# 0_96OLED_SSD1315.net
KiCad netlist of a schematic drawn in Altium Designer
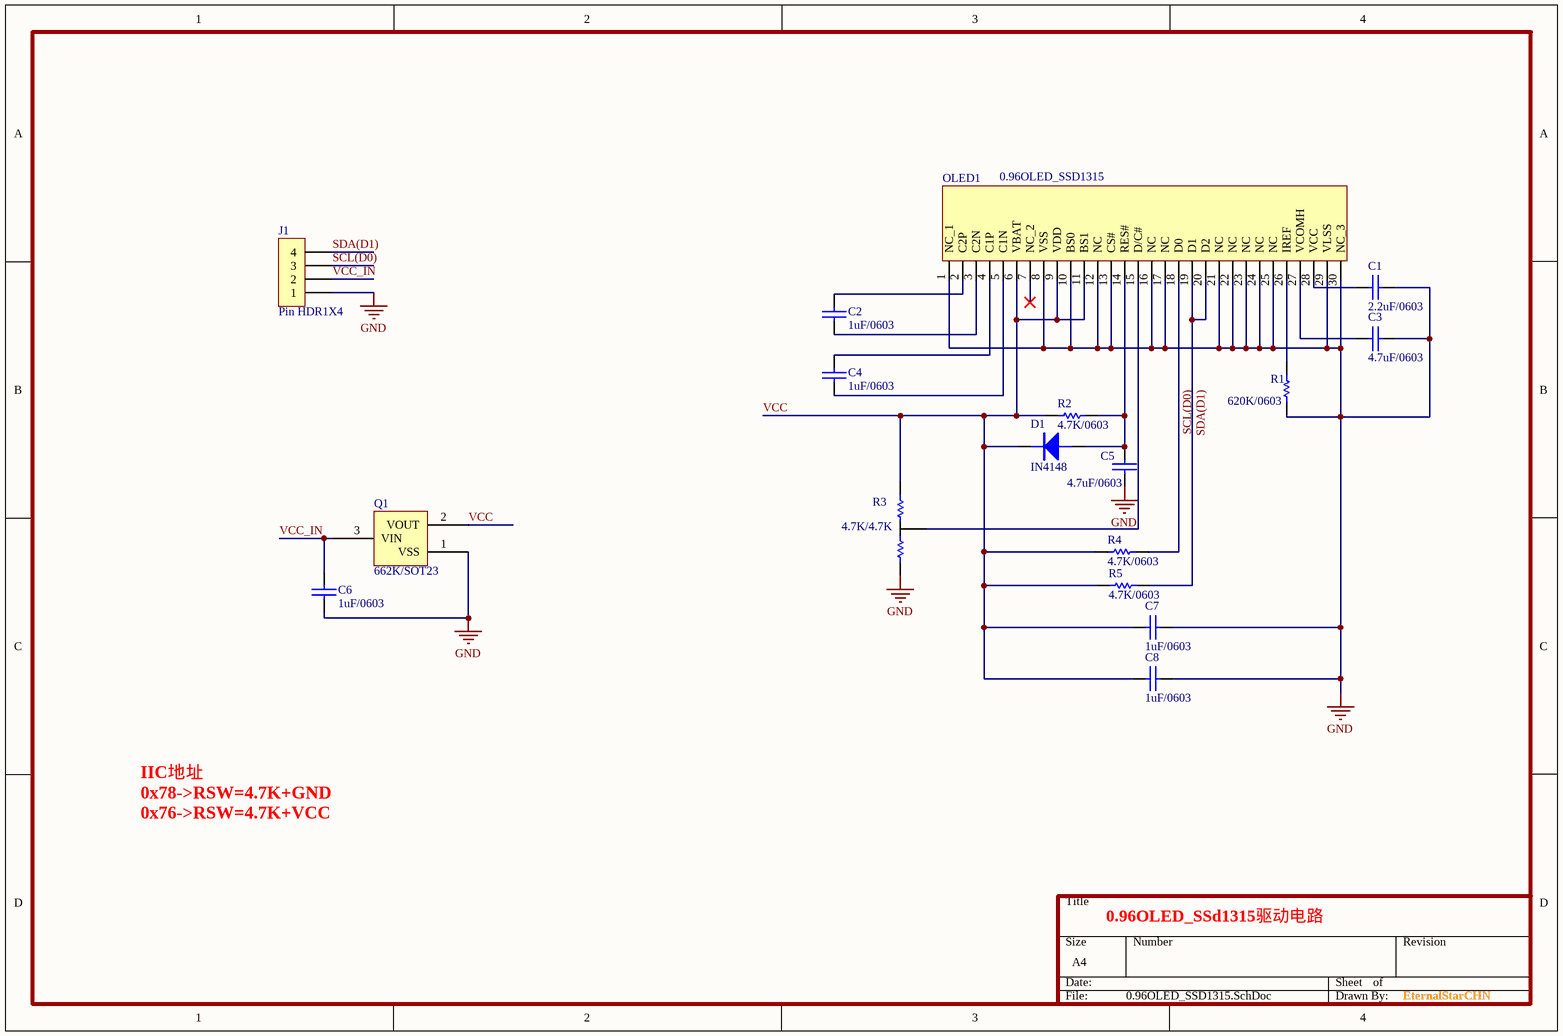
[diagram p0: 0.96OLED_SSD1315.SchDoc]

(export (version "E")
  (design (tool "Eeschema 10.0.6"))
  (components
    (comp (ref "C1")
      (value "2.2uF/0603")
      (footprint "0603C")
      (description "无极性电容")
      (libsource (lib "电容") (part "CAP"))
    )
    (comp (ref "C2")
      (value "1uF/0603")
      (footprint "0603C")
      (description "无极性电容")
      (libsource (lib "电容") (part "CAP"))
    )
    (comp (ref "C3")
      (value "4.7uF/0603")
      (footprint "0603C")
      (description "无极性电容")
      (libsource (lib "电容") (part "CAP"))
    )
    (comp (ref "C4")
      (value "1uF/0603")
      (footprint "0603C")
      (description "无极性电容")
      (libsource (lib "电容") (part "CAP"))
    )
    (comp (ref "C5")
      (value "4.7uF/0603")
      (footprint "0603C")
      (description "无极性电容")
      (libsource (lib "电容") (part "CAP"))
    )
    (comp (ref "C6")
      (value "1uF/0603")
      (footprint "0603C")
      (description "无极性电容")
      (libsource (lib "电容") (part "CAP"))
    )
    (comp (ref "C7")
      (value "1uF/0603")
      (footprint "0603C")
      (description "无极性电容")
      (libsource (lib "电容") (part "CAP"))
    )
    (comp (ref "C8")
      (value "1uF/0603")
      (footprint "0603C")
      (description "无极性电容")
      (libsource (lib "电容") (part "CAP"))
    )
    (comp (ref "D1")
      (value "IN4148")
      (footprint "SOD-523")
      (description "普通二极管")
      (libsource (lib "二极管") (part "DIODE"))
    )
    (comp (ref "J1")
      (value "Pin HDR1X4")
      (footprint "Pin HDR1X4/2.54mm-S")
      (libsource (lib "排针") (part "Pin HDR1X4"))
    )
    (comp (ref "OLED1")
      (value "0.96OLED_SSD1315")
      (footprint "OLED_0.96")
      (libsource (lib "LCD") (part "0.96OLED_SSD1315"))
    )
    (comp (ref "Q1")
      (value "662K/SOT23")
      (footprint "SOT23")
      (description "SOT23封装LDO")
      (libsource (lib "电源芯片") (part "LDO_SOT23"))
    )
    (comp (ref "R1") (value "620K/0603") (footprint "0603R") (libsource (lib "电阻") (part "RES")))
    (comp (ref "R2") (value "4.7K/0603") (footprint "0603R") (libsource (lib "电阻") (part "RES")))
    (comp (ref "R3") (value "4.7K/4.7K") (footprint "SW_0603R") (libsource (lib "电阻") (part "RES_SW")))
    (comp (ref "R4") (value "4.7K/0603") (footprint "0603R") (libsource (lib "电阻") (part "RES")))
    (comp (ref "R5") (value "4.7K/0603") (footprint "0603R") (libsource (lib "电阻") (part "RES")))
  )
  (nets
    (net (code "1") (name "/SCL(D0)") (class "Default")
      (node (ref "J1") (pin "3") (pinfunction "3_3") (pintype "passive"))
      (node (ref "OLED1") (pin "18") (pinfunction "D0_18") (pintype "passive"))
      (node (ref "R4") (pin "1") (pinfunction "1_1") (pintype "passive"))
    )
    (net (code "2") (name "/SDA(D1)") (class "Default")
      (node (ref "J1") (pin "4") (pinfunction "4_4") (pintype "passive"))
      (node (ref "OLED1") (pin "19") (pinfunction "D1_19") (pintype "passive"))
      (node (ref "OLED1") (pin "20") (pinfunction "D2_20") (pintype "passive"))
      (node (ref "R5") (pin "1") (pinfunction "1_1") (pintype "passive"))
    )
    (net (code "3") (name "/VCC") (class "Default")
      (node (ref "C7") (pin "2") (pinfunction "2_2") (pintype "passive"))
      (node (ref "C8") (pin "2") (pinfunction "2_2") (pintype "passive"))
      (node (ref "D1") (pin "K") (pinfunction "K_K") (pintype "passive"))
      (node (ref "OLED1") (pin "11") (pinfunction "BS1_11") (pintype "passive"))
      (node (ref "OLED1") (pin "6") (pinfunction "VBAT_6") (pintype "passive"))
      (node (ref "OLED1") (pin "9") (pinfunction "VDD_9") (pintype "passive"))
      (node (ref "Q1") (pin "2") (pinfunction "VOUT_2") (pintype "passive"))
      (node (ref "R2") (pin "2") (pinfunction "2_2") (pintype "passive"))
      (node (ref "R3") (pin "1") (pinfunction "1_1") (pintype "passive"))
      (node (ref "R4") (pin "2") (pinfunction "2_2") (pintype "passive"))
      (node (ref "R5") (pin "2") (pinfunction "2_2") (pintype "passive"))
    )
    (net (code "4") (name "/VCC_IN") (class "Default")
      (node (ref "C6") (pin "1") (pinfunction "1_1") (pintype "passive"))
      (node (ref "J1") (pin "2") (pinfunction "2_2") (pintype "passive"))
      (node (ref "Q1") (pin "3") (pinfunction "VIN_3") (pintype "passive"))
    )
    (net (code "5") (name "GND") (class "Default")
      (node (ref "C1") (pin "1") (pinfunction "1_1") (pintype "passive"))
      (node (ref "C3") (pin "1") (pinfunction "1_1") (pintype "passive"))
      (node (ref "C5") (pin "1") (pinfunction "1_1") (pintype "passive"))
      (node (ref "C6") (pin "2") (pinfunction "2_2") (pintype "passive"))
      (node (ref "C7") (pin "1") (pinfunction "1_1") (pintype "passive"))
      (node (ref "C8") (pin "1") (pinfunction "1_1") (pintype "passive"))
      (node (ref "J1") (pin "1") (pinfunction "1_1") (pintype "passive"))
      (node (ref "OLED1") (pin "1") (pinfunction "NC_1_1") (pintype "passive"))
      (node (ref "OLED1") (pin "10") (pinfunction "BS0_10") (pintype "passive"))
      (node (ref "OLED1") (pin "12") (pinfunction "NC_12") (pintype "passive"))
      (node (ref "OLED1") (pin "13") (pinfunction "CS#_13") (pintype "passive"))
      (node (ref "OLED1") (pin "16") (pinfunction "NC_16") (pintype "passive"))
      (node (ref "OLED1") (pin "17") (pinfunction "NC_17") (pintype "passive"))
      (node (ref "OLED1") (pin "21") (pinfunction "NC_21") (pintype "passive"))
      (node (ref "OLED1") (pin "22") (pinfunction "NC_22") (pintype "passive"))
      (node (ref "OLED1") (pin "23") (pinfunction "NC_23") (pintype "passive"))
      (node (ref "OLED1") (pin "24") (pinfunction "NC_24") (pintype "passive"))
      (node (ref "OLED1") (pin "25") (pinfunction "NC_25") (pintype "passive"))
      (node (ref "OLED1") (pin "29") (pinfunction "VLSS_29") (pintype "passive"))
      (node (ref "OLED1") (pin "30") (pinfunction "NC_3_30") (pintype "passive"))
      (node (ref "OLED1") (pin "8") (pinfunction "VSS_8") (pintype "passive"))
      (node (ref "Q1") (pin "1") (pinfunction "VSS_1") (pintype "passive"))
      (node (ref "R1") (pin "1") (pinfunction "1_1") (pintype "passive"))
      (node (ref "R3") (pin "3") (pinfunction "3_3") (pintype "passive"))
    )
    (net (code "6") (name "Net-(OLED1-C1N)") (class "Default")
      (node (ref "C4") (pin "1") (pinfunction "1_1") (pintype "passive"))
      (node (ref "OLED1") (pin "5") (pinfunction "C1N_5") (pintype "passive"))
    )
    (net (code "7") (name "Net-(OLED1-C1P)") (class "Default")
      (node (ref "C4") (pin "2") (pinfunction "2_2") (pintype "passive"))
      (node (ref "OLED1") (pin "4") (pinfunction "C1P_4") (pintype "passive"))
    )
    (net (code "8") (name "Net-(OLED1-C2N)") (class "Default")
      (node (ref "C2") (pin "1") (pinfunction "1_1") (pintype "passive"))
      (node (ref "OLED1") (pin "3") (pinfunction "C2N_3") (pintype "passive"))
    )
    (net (code "9") (name "Net-(OLED1-C2P)") (class "Default")
      (node (ref "C2") (pin "2") (pinfunction "2_2") (pintype "passive"))
      (node (ref "OLED1") (pin "2") (pinfunction "C2P_2") (pintype "passive"))
    )
    (net (code "10") (name "Net-(OLED1-D{slash}C#)") (class "Default")
      (node (ref "OLED1") (pin "15") (pinfunction "D/C#_15") (pintype "passive"))
      (node (ref "R3") (pin "2") (pinfunction "2_2") (pintype "passive"))
    )
    (net (code "11") (name "Net-(OLED1-IREF)") (class "Default")
      (node (ref "OLED1") (pin "26") (pinfunction "IREF_26") (pintype "passive"))
      (node (ref "R1") (pin "2") (pinfunction "2_2") (pintype "passive"))
    )
    (net (code "12") (name "Net-(OLED1-RES#)") (class "Default")
      (node (ref "C5") (pin "2") (pinfunction "2_2") (pintype "passive"))
      (node (ref "D1") (pin "A") (pinfunction "A_A") (pintype "passive"))
      (node (ref "OLED1") (pin "14") (pinfunction "RES#_14") (pintype "passive"))
      (node (ref "R2") (pin "1") (pinfunction "1_1") (pintype "passive"))
    )
    (net (code "13") (name "Net-(OLED1-VCC)") (class "Default")
      (node (ref "C1") (pin "2") (pinfunction "2_2") (pintype "passive"))
      (node (ref "OLED1") (pin "28") (pinfunction "VCC_28") (pintype "passive"))
    )
    (net (code "14") (name "Net-(OLED1-VCOMH)") (class "Default")
      (node (ref "C3") (pin "2") (pinfunction "2_2") (pintype "passive"))
      (node (ref "OLED1") (pin "27") (pinfunction "VCOMH_27") (pintype "passive"))
    )
    (net (code "15") (name "unconnected-(OLED1-NC_2-Pad7)") (class "Default")
      (node (ref "OLED1") (pin "7") (pinfunction "NC_2_7") (pintype "passive+no_connect"))
    )
  )
)
